# SCH_BrightHackerCard.net
KiCad netlist of a schematic drawn in EasyEDA
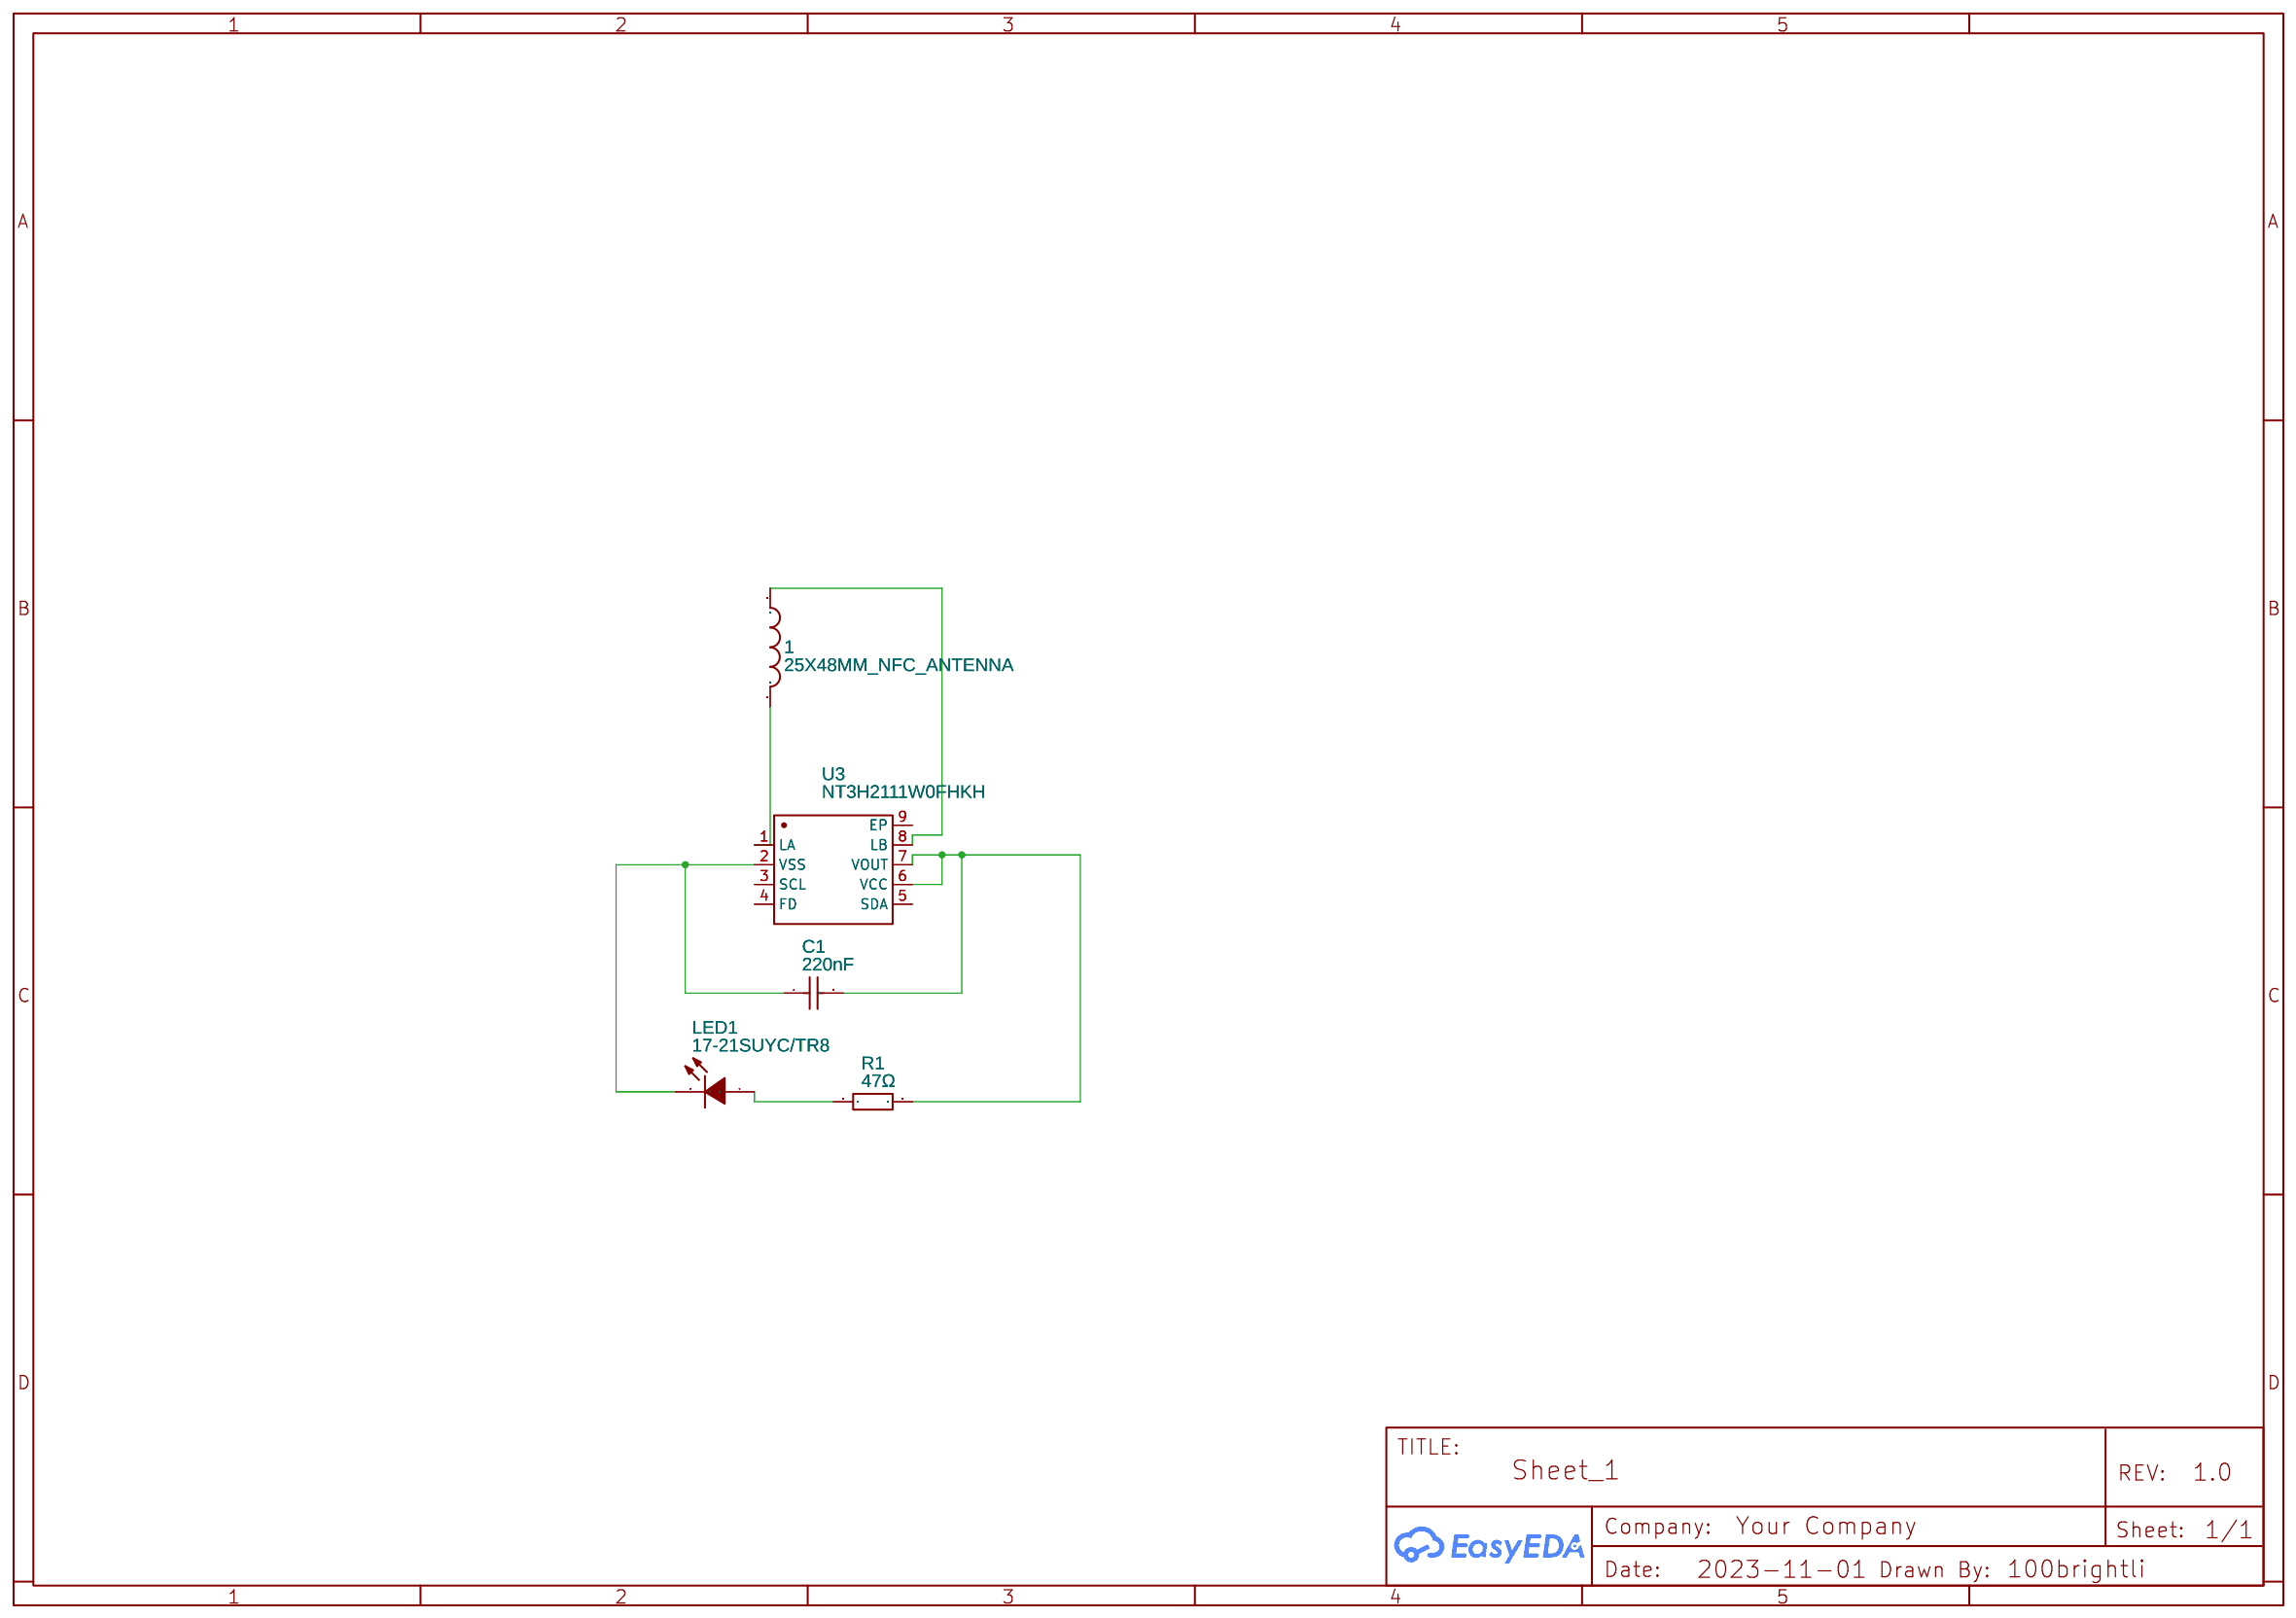
[diagram p0: schematic sheet]

(export (version "E")
  (design (tool "Eeschema 10.0.6"))
  (components
    (comp (ref "1") (value "25X48MM_NFC_ANTENNA") (libsource (lib "") (part "25X48MM_NFC_ANTENNA")))
    (comp (ref "C1")
      (value "220nF")
      (fields
        (field (name "Manufacturer Part") "CL10B224KA8NNNC")
        (field (name "Manufacturer") "SAMSUNG(三星)")
      )
      (libsource (lib "") (part "CL10B224KA8NNNC"))
    )
    (comp (ref "LED1")
      (value "17-21SUYC/TR8")
      (fields (field (name "Manufacturer Part") "KT-0805黄灯") (field (name "Manufacturer") "KENTO"))
      (libsource (lib "") (part "17-21SUYC/TR8"))
    )
    (comp (ref "R1")
      (value "47Ω")
      (fields
        (field (name "Manufacturer Part") "0603WAF470JT5E")
        (field (name "Manufacturer") "UNI-ROYAL(厚声)")
      )
      (libsource (lib "") (part "0603WAF470JT5E"))
    )
    (comp (ref "U3")
      (value "NT3H2111W0FHKH")
      (fields (field (name "Manufacturer") "NXP(恩智浦)"))
      (libsource (lib "") (part "NT3H2111W0FHKH"))
    )
  )
  (nets
    (net (code "1") (name "Net-(LED1-+)") (class "Default")
      (node (ref "LED1") (pin "1") (pinfunction "+_1") (pintype "unspecified"))
      (node (ref "R1") (pin "1") (pinfunction "1_1") (pintype "input"))
    )
    (net (code "2") (name "Net-(LED1--)") (class "Default")
      (node (ref "C1") (pin "1") (pinfunction "1_1") (pintype "input"))
      (node (ref "LED1") (pin "2") (pinfunction "-_2") (pintype "unspecified"))
      (node (ref "U3") (pin "2") (pinfunction "VSS_2") (pintype "unspecified"))
    )
    (net (code "3") (name "Net-(U3-LA)") (class "Default")
      (node (ref "1") (pin "P$2") (pinfunction "P$2_P$2") (pintype "bidirectional"))
      (node (ref "U3") (pin "1") (pinfunction "LA_1") (pintype "unspecified"))
    )
    (net (code "4") (name "Net-(U3-LB)") (class "Default")
      (node (ref "1") (pin "P$1") (pinfunction "P$1_P$1") (pintype "bidirectional"))
      (node (ref "U3") (pin "8") (pinfunction "LB_8") (pintype "unspecified"))
    )
    (net (code "5") (name "Net-(U3-VCC)") (class "Default")
      (node (ref "C1") (pin "2") (pinfunction "2_2") (pintype "input"))
      (node (ref "R1") (pin "2") (pinfunction "2_2") (pintype "input"))
      (node (ref "U3") (pin "6") (pinfunction "VCC_6") (pintype "unspecified"))
      (node (ref "U3") (pin "7") (pinfunction "VOUT_7") (pintype "unspecified"))
    )
    (net (code "6") (name "unconnected-(U3-EP-Pad9)") (class "Default")
      (node (ref "U3") (pin "9") (pinfunction "EP_9") (pintype "unspecified"))
    )
    (net (code "7") (name "unconnected-(U3-FD-Pad4)") (class "Default")
      (node (ref "U3") (pin "4") (pinfunction "FD_4") (pintype "unspecified"))
    )
    (net (code "8") (name "unconnected-(U3-SCL-Pad3)") (class "Default")
      (node (ref "U3") (pin "3") (pinfunction "SCL_3") (pintype "unspecified"))
    )
    (net (code "9") (name "unconnected-(U3-SDA-Pad5)") (class "Default")
      (node (ref "U3") (pin "5") (pinfunction "SDA_5") (pintype "unspecified"))
    )
  )
)
